# Power.net
KiCad netlist of a schematic drawn in Altium Designer
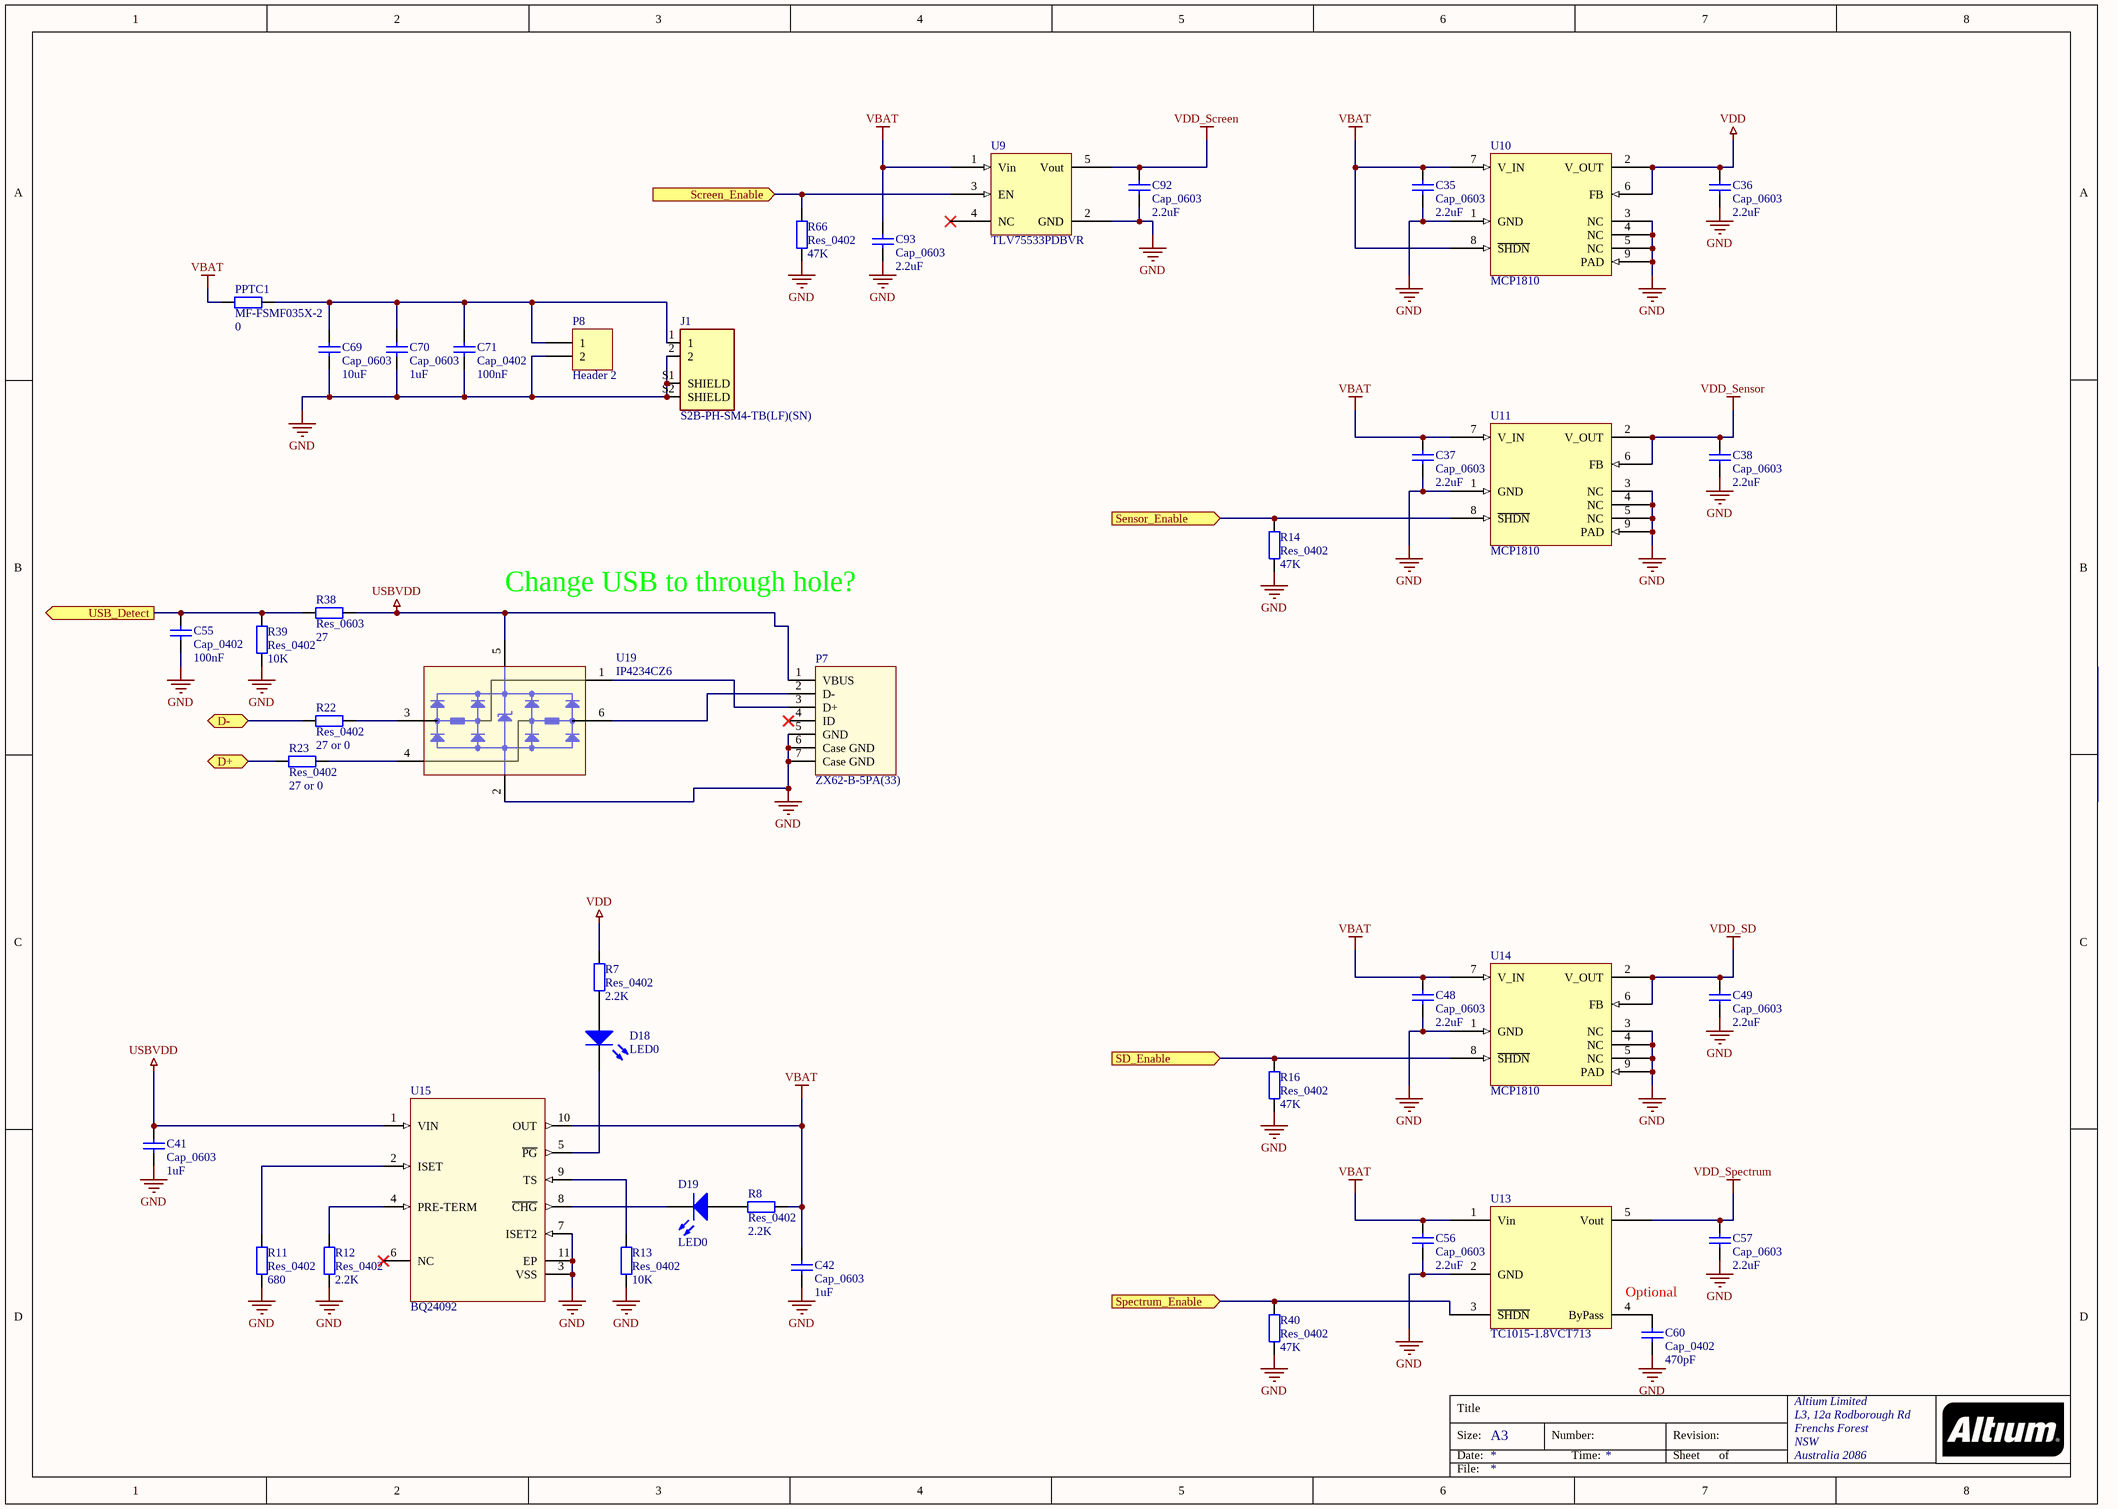
[diagram p0: Power.SchDoc]

(export (version "E")
  (design (tool "Eeschema 10.0.6"))
  (components
    (comp (ref "C35")
      (value "Cap_0603")
      (footprint "0603")
      (description "Capacitor")
      (fields (field (name "ALTIUM_VALUE") "2.2uF") (field (name "PUBLISHER") "Altium Limited"))
      (libsource (lib "Schematic_Components") (part "Cap_0603"))
    )
    (comp (ref "C36")
      (value "Cap_0603")
      (footprint "0603")
      (description "Capacitor")
      (fields (field (name "ALTIUM_VALUE") "2.2uF") (field (name "PUBLISHER") "Altium Limited"))
      (libsource (lib "Schematic_Components") (part "Cap_0603"))
    )
    (comp (ref "C37")
      (value "Cap_0603")
      (footprint "0603")
      (description "Capacitor")
      (fields (field (name "ALTIUM_VALUE") "2.2uF") (field (name "PUBLISHER") "Altium Limited"))
      (libsource (lib "Schematic_Components") (part "Cap_0603"))
    )
    (comp (ref "C38")
      (value "Cap_0603")
      (footprint "0603")
      (description "Capacitor")
      (fields (field (name "ALTIUM_VALUE") "2.2uF") (field (name "PUBLISHER") "Altium Limited"))
      (libsource (lib "Schematic_Components") (part "Cap_0603"))
    )
    (comp (ref "C41")
      (value "Cap_0603")
      (footprint "0603")
      (description "Capacitor")
      (fields (field (name "ALTIUM_VALUE") "1uF") (field (name "PUBLISHER") "Altium Limited"))
      (libsource (lib "Schematic_Components") (part "Cap_0603"))
    )
    (comp (ref "C42")
      (value "Cap_0603")
      (footprint "0603")
      (description "Capacitor")
      (fields (field (name "ALTIUM_VALUE") "1uF") (field (name "PUBLISHER") "Altium Limited"))
      (libsource (lib "Schematic_Components") (part "Cap_0603"))
    )
    (comp (ref "C48")
      (value "Cap_0603")
      (footprint "0603")
      (description "Capacitor")
      (fields (field (name "ALTIUM_VALUE") "2.2uF") (field (name "PUBLISHER") "Altium Limited"))
      (libsource (lib "Schematic_Components") (part "Cap_0603"))
    )
    (comp (ref "C49")
      (value "Cap_0603")
      (footprint "0603")
      (description "Capacitor")
      (fields (field (name "ALTIUM_VALUE") "2.2uF") (field (name "PUBLISHER") "Altium Limited"))
      (libsource (lib "Schematic_Components") (part "Cap_0603"))
    )
    (comp (ref "C55")
      (value "Cap_0402")
      (footprint "0402")
      (description "Capacitor")
      (fields (field (name "ALTIUM_VALUE") "100nF") (field (name "PUBLISHER") "Altium Limited"))
      (libsource (lib "Schematic_Components") (part "Cap_0402"))
    )
    (comp (ref "C56")
      (value "Cap_0603")
      (footprint "0603")
      (description "Capacitor")
      (fields (field (name "ALTIUM_VALUE") "2.2uF") (field (name "PUBLISHER") "Altium Limited"))
      (libsource (lib "Schematic_Components") (part "Cap_0603"))
    )
    (comp (ref "C57")
      (value "Cap_0603")
      (footprint "0603")
      (description "Capacitor")
      (fields (field (name "ALTIUM_VALUE") "2.2uF") (field (name "PUBLISHER") "Altium Limited"))
      (libsource (lib "Schematic_Components") (part "Cap_0603"))
    )
    (comp (ref "C60")
      (value "Cap_0402")
      (footprint "0402")
      (description "Capacitor")
      (fields (field (name "ALTIUM_VALUE") "470pF") (field (name "PUBLISHER") "Altium Limited"))
      (libsource (lib "Schematic_Components") (part "Cap_0402"))
    )
    (comp (ref "C69")
      (value "Cap_0603")
      (footprint "0603")
      (description "Capacitor")
      (fields (field (name "ALTIUM_VALUE") "10uF") (field (name "PUBLISHER") "Altium Limited"))
      (libsource (lib "Schematic_Components") (part "Cap_0603"))
    )
    (comp (ref "C70")
      (value "Cap_0603")
      (footprint "0603")
      (description "Capacitor")
      (fields (field (name "ALTIUM_VALUE") "1uF") (field (name "PUBLISHER") "Altium Limited"))
      (libsource (lib "Schematic_Components") (part "Cap_0603"))
    )
    (comp (ref "C71")
      (value "Cap_0402")
      (footprint "0402")
      (description "Capacitor")
      (fields (field (name "ALTIUM_VALUE") "100nF") (field (name "PUBLISHER") "Altium Limited"))
      (libsource (lib "Schematic_Components") (part "Cap_0402"))
    )
    (comp (ref "C92")
      (value "Cap_0603")
      (footprint "0603")
      (description "Capacitor")
      (fields (field (name "ALTIUM_VALUE") "2.2uF") (field (name "PUBLISHER") "Altium Limited"))
      (libsource (lib "Schematic_Components") (part "Cap_0603"))
    )
    (comp (ref "C93")
      (value "Cap_0603")
      (footprint "0603")
      (description "Capacitor")
      (fields (field (name "ALTIUM_VALUE") "2.2uF") (field (name "PUBLISHER") "Altium Limited"))
      (libsource (lib "Schematic_Components") (part "Cap_0603"))
    )
    (comp (ref "D18")
      (value "LED0")
      (footprint "0603")
      (description "Typical INFRARED GaAs LED")
      (fields (field (name "PUBLISHER") "Altium Limited"))
      (libsource (lib "Schematic_Components") (part "LED0"))
    )
    (comp (ref "D19")
      (value "LED0")
      (footprint "0603")
      (description "Typical INFRARED GaAs LED")
      (fields (field (name "PUBLISHER") "Altium Limited"))
      (libsource (lib "Schematic_Components") (part "LED0"))
    )
    (comp (ref "J1")
      (value "S2B-PH-SM4-TB(LF)(SN)")
      (footprint "JST_S2B-PH-SM4-TB(LF)(SN)")
      (description "PH Series 2 Position 2 mm Pitch Surface Mount Side Entry Shrouded Header")
      (fields (field (name "MF") "{'manufacturer': u'JST Sales'}"))
      (libsource (lib "Schematic_Components") (part "S2B-PH-SM4-TB(LF)(SN)"))
    )
    (comp (ref "P7")
      (value "ZX62-B-5PA(33)")
      (footprint "ZX62-B-5PA(33)")
      (description "USB Connector")
      (libsource (lib "Exeger_schematic_library") (part "ZX62-B-5PA(33)"))
    )
    (comp (ref "P8")
      (value "Header 2")
      (footprint "HDR1X2")
      (description "Header, 2-Pin")
      (fields (field (name "PUBLISHER") "Altium Limited"))
      (libsource (lib "Miscellaneous Connectors") (part "Header 2"))
    )
    (comp (ref "PPTC1")
      (value "MF-FSMF035X-2")
      (footprint "0603")
      (description "PPTC_0603")
      (fields (field (name "ALTIUM_VALUE") "0") (field (name "PUBLISHER") "Altium Limited"))
      (libsource (lib "Schematic_Components") (part "MF-FSMF035X-2"))
    )
    (comp (ref "R7")
      (value "Res_0402")
      (footprint "0402")
      (description "Resistor")
      (fields (field (name "ALTIUM_VALUE") "2.2K") (field (name "PUBLISHER") "Altium Limited"))
      (libsource (lib "") (part "Res_0402_1"))
    )
    (comp (ref "R8")
      (value "Res_0402")
      (footprint "0402")
      (description "Resistor")
      (fields (field (name "ALTIUM_VALUE") "2.2K") (field (name "PUBLISHER") "Altium Limited"))
      (libsource (lib "Schematic_Components") (part "Res_0402"))
    )
    (comp (ref "R11")
      (value "Res_0402")
      (footprint "0402")
      (description "Resistor")
      (fields (field (name "ALTIUM_VALUE") "680") (field (name "PUBLISHER") "Altium Limited"))
      (libsource (lib "") (part "Res_0402_1"))
    )
    (comp (ref "R12")
      (value "Res_0402")
      (footprint "0402")
      (description "Resistor")
      (fields (field (name "ALTIUM_VALUE") "2.2K") (field (name "PUBLISHER") "Altium Limited"))
      (libsource (lib "") (part "Res_0402_1"))
    )
    (comp (ref "R13")
      (value "Res_0402")
      (footprint "0402")
      (description "Resistor")
      (fields (field (name "ALTIUM_VALUE") "10K") (field (name "PUBLISHER") "Altium Limited"))
      (libsource (lib "") (part "Res_0402_1"))
    )
    (comp (ref "R14")
      (value "Res_0402")
      (footprint "0402")
      (description "Resistor")
      (fields (field (name "ALTIUM_VALUE") "47K") (field (name "PUBLISHER") "Altium Limited"))
      (libsource (lib "") (part "Res_0402_3"))
    )
    (comp (ref "R16")
      (value "Res_0402")
      (footprint "0402")
      (description "Resistor")
      (fields (field (name "ALTIUM_VALUE") "47K") (field (name "PUBLISHER") "Altium Limited"))
      (libsource (lib "") (part "Res_0402_1"))
    )
    (comp (ref "R22")
      (value "Res_0402")
      (footprint "0402")
      (description "Resistor")
      (fields (field (name "ALTIUM_VALUE") "27 or 0") (field (name "PUBLISHER") "Altium Limited"))
      (libsource (lib "") (part "Res_0402_2"))
    )
    (comp (ref "R23")
      (value "Res_0402")
      (footprint "0402")
      (description "Resistor")
      (fields (field (name "ALTIUM_VALUE") "27 or 0") (field (name "PUBLISHER") "Altium Limited"))
      (libsource (lib "") (part "Res_0402_2"))
    )
    (comp (ref "R38")
      (value "Res_0603")
      (footprint "0603")
      (description "Resistor")
      (fields (field (name "ALTIUM_VALUE") "27") (field (name "PUBLISHER") "Altium Limited"))
      (libsource (lib "Schematic_Components") (part "Res_0603"))
    )
    (comp (ref "R39")
      (value "Res_0402")
      (footprint "0402")
      (description "Resistor")
      (fields (field (name "ALTIUM_VALUE") "10K") (field (name "PUBLISHER") "Altium Limited"))
      (libsource (lib "") (part "Res_0402_1"))
    )
    (comp (ref "R40")
      (value "Res_0402")
      (footprint "0402")
      (description "Resistor")
      (fields (field (name "ALTIUM_VALUE") "47K") (field (name "PUBLISHER") "Altium Limited"))
      (libsource (lib "") (part "Res_0402_3"))
    )
    (comp (ref "R66")
      (value "Res_0402")
      (footprint "0402")
      (description "Resistor")
      (fields (field (name "ALTIUM_VALUE") "47K") (field (name "PUBLISHER") "Altium Limited"))
      (libsource (lib "") (part "Res_0402_3"))
    )
    (comp (ref "U9")
      (value "TLV75533PDBVR")
      (footprint "SOT-23 (5)")
      (description "3.3V regulator")
      (libsource (lib "Schematic_Components") (part "TLV75533PDBVR"))
    )
    (comp (ref "U10")
      (value "MCP1810")
      (footprint "VDFN8")
      (description "3V Regulator, 150 mA")
      (libsource (lib "Schematic_Components") (part "MCP1810"))
    )
    (comp (ref "U11")
      (value "MCP1810")
      (footprint "VDFN8")
      (description "3V Regulator, 150 mA")
      (libsource (lib "Schematic_Components") (part "MCP1810"))
    )
    (comp (ref "U13")
      (value "TC1015-1.8VCT713")
      (footprint "SOT-23 (5)")
      (description "1.8V Regulator")
      (libsource (lib "Schematic_Components") (part "TC1015-1.8VCT713"))
    )
    (comp (ref "U14")
      (value "MCP1810")
      (footprint "VDFN8")
      (description "3V Regulator, 150 mA")
      (libsource (lib "Schematic_Components") (part "MCP1810"))
    )
    (comp (ref "U15")
      (value "BQ24092")
      (footprint "HVSSOP-10")
      (description "Battery Charger")
      (libsource (lib "Schematic_Components") (part "BQ24092"))
    )
    (comp (ref "U19")
      (value "IP4234CZ6")
      (footprint "TSOP95P280X110_HS-7N")
      (description "USB Line Protection")
      (libsource (lib "Exeger_schematic_library") (part "IP4234CZ6"))
    )
  )
  (nets
    (net (code "1") (name "/D+") (class "Default")
      (node (ref "R23") (pin "1") (pinfunction "1_1") (pintype "passive"))
    )
    (net (code "2") (name "/D-") (class "Default")
      (node (ref "R22") (pin "1") (pinfunction "1_1") (pintype "passive"))
    )
    (net (code "3") (name "/SD_Enable") (class "Default")
      (node (ref "R16") (pin "2") (pinfunction "2_2") (pintype "passive"))
      (node (ref "U14") (pin "8") (pinfunction "~{SHDN}_8") (pintype "input"))
    )
    (net (code "4") (name "/Screen_Enable") (class "Default")
      (node (ref "R66") (pin "1") (pinfunction "1_1") (pintype "passive"))
      (node (ref "U9") (pin "3") (pinfunction "EN_3") (pintype "input"))
    )
    (net (code "5") (name "/Sensor_Enable") (class "Default")
      (node (ref "R14") (pin "1") (pinfunction "1_1") (pintype "passive"))
      (node (ref "U11") (pin "8") (pinfunction "~{SHDN}_8") (pintype "input"))
    )
    (net (code "6") (name "/Spectrum_Enable") (class "Default")
      (node (ref "R40") (pin "1") (pinfunction "1_1") (pintype "passive"))
      (node (ref "U13") (pin "3") (pinfunction "~{SHDN}_3") (pintype "passive"))
    )
    (net (code "7") (name "/USB_Detect") (class "Default")
      (node (ref "C55") (pin "2") (pinfunction "2_2") (pintype "passive"))
      (node (ref "R38") (pin "1") (pinfunction "1_1") (pintype "passive"))
      (node (ref "R39") (pin "2") (pinfunction "2_2") (pintype "passive"))
    )
    (net (code "8") (name "GND") (class "Default")
      (node (ref "C35") (pin "1") (pinfunction "1_1") (pintype "passive"))
      (node (ref "C36") (pin "1") (pinfunction "1_1") (pintype "passive"))
      (node (ref "C37") (pin "1") (pinfunction "1_1") (pintype "passive"))
      (node (ref "C38") (pin "1") (pinfunction "1_1") (pintype "passive"))
      (node (ref "C41") (pin "1") (pinfunction "1_1") (pintype "passive"))
      (node (ref "C42") (pin "1") (pinfunction "1_1") (pintype "passive"))
      (node (ref "C48") (pin "1") (pinfunction "1_1") (pintype "passive"))
      (node (ref "C49") (pin "1") (pinfunction "1_1") (pintype "passive"))
      (node (ref "C55") (pin "1") (pinfunction "1_1") (pintype "passive"))
      (node (ref "C56") (pin "1") (pinfunction "1_1") (pintype "passive"))
      (node (ref "C57") (pin "1") (pinfunction "1_1") (pintype "passive"))
      (node (ref "C60") (pin "1") (pinfunction "1_1") (pintype "passive"))
      (node (ref "C69") (pin "1") (pinfunction "1_1") (pintype "passive"))
      (node (ref "C70") (pin "1") (pinfunction "1_1") (pintype "passive"))
      (node (ref "C71") (pin "1") (pinfunction "1_1") (pintype "passive"))
      (node (ref "C92") (pin "1") (pinfunction "1_1") (pintype "passive"))
      (node (ref "C93") (pin "1") (pinfunction "1_1") (pintype "passive"))
      (node (ref "J1") (pin "2") (pinfunction "2_2") (pintype "passive"))
      (node (ref "J1") (pin "S1") (pinfunction "SHIELD_S1") (pintype "passive"))
      (node (ref "J1") (pin "S2") (pinfunction "SHIELD_S2") (pintype "passive"))
      (node (ref "P7") (pin "5") (pinfunction "GND_5") (pintype "power_in"))
      (node (ref "P7") (pin "6") (pinfunction "Case_GND_6") (pintype "power_in"))
      (node (ref "P7") (pin "7") (pinfunction "Case_GND_7") (pintype "passive"))
      (node (ref "P8") (pin "2") (pinfunction "2_2") (pintype "passive"))
      (node (ref "R11") (pin "1") (pinfunction "1_1") (pintype "passive"))
      (node (ref "R12") (pin "1") (pinfunction "1_1") (pintype "passive"))
      (node (ref "R13") (pin "1") (pinfunction "1_1") (pintype "passive"))
      (node (ref "R14") (pin "2") (pinfunction "2_2") (pintype "passive"))
      (node (ref "R16") (pin "1") (pinfunction "1_1") (pintype "passive"))
      (node (ref "R39") (pin "1") (pinfunction "1_1") (pintype "passive"))
      (node (ref "R40") (pin "2") (pinfunction "2_2") (pintype "passive"))
      (node (ref "R66") (pin "2") (pinfunction "2_2") (pintype "passive"))
      (node (ref "U10") (pin "1") (pinfunction "GND_1") (pintype "input"))
      (node (ref "U10") (pin "3") (pinfunction "NC_3") (pintype "passive"))
      (node (ref "U10") (pin "4") (pinfunction "NC_4") (pintype "passive"))
      (node (ref "U10") (pin "5") (pinfunction "NC_5") (pintype "passive"))
      (node (ref "U10") (pin "9") (pinfunction "PAD_9") (pintype "input"))
      (node (ref "U11") (pin "1") (pinfunction "GND_1") (pintype "input"))
      (node (ref "U11") (pin "3") (pinfunction "NC_3") (pintype "passive"))
      (node (ref "U11") (pin "4") (pinfunction "NC_4") (pintype "passive"))
      (node (ref "U11") (pin "5") (pinfunction "NC_5") (pintype "passive"))
      (node (ref "U11") (pin "9") (pinfunction "PAD_9") (pintype "input"))
      (node (ref "U13") (pin "2") (pinfunction "GND_2") (pintype "passive"))
      (node (ref "U14") (pin "1") (pinfunction "GND_1") (pintype "input"))
      (node (ref "U14") (pin "3") (pinfunction "NC_3") (pintype "passive"))
      (node (ref "U14") (pin "4") (pinfunction "NC_4") (pintype "passive"))
      (node (ref "U14") (pin "5") (pinfunction "NC_5") (pintype "passive"))
      (node (ref "U14") (pin "9") (pinfunction "PAD_9") (pintype "input"))
      (node (ref "U15") (pin "11") (pinfunction "EP_11") (pintype "power_in"))
      (node (ref "U15") (pin "3") (pinfunction "VSS_3") (pintype "power_in"))
      (node (ref "U15") (pin "7") (pinfunction "ISET2_7") (pintype "input"))
      (node (ref "U19") (pin "2") (pinfunction "GND_2") (pintype "power_in"))
      (node (ref "U9") (pin "2") (pinfunction "GND_2") (pintype "passive"))
    )
    (net (code "9") (name "Net-(C69-Pad2)") (class "Default")
      (node (ref "C69") (pin "2") (pinfunction "2_2") (pintype "passive"))
      (node (ref "C70") (pin "2") (pinfunction "2_2") (pintype "passive"))
      (node (ref "C71") (pin "2") (pinfunction "2_2") (pintype "passive"))
      (node (ref "J1") (pin "1") (pinfunction "1_1") (pintype "passive"))
      (node (ref "P8") (pin "1") (pinfunction "1_1") (pintype "passive"))
      (node (ref "PPTC1") (pin "2") (pinfunction "2_2") (pintype "passive"))
    )
    (net (code "10") (name "Net-(D18-A)") (class "Default")
      (node (ref "D18") (pin "2") (pinfunction "A_2") (pintype "passive"))
      (node (ref "R7") (pin "1") (pinfunction "1_1") (pintype "passive"))
    )
    (net (code "11") (name "Net-(D18-K)") (class "Default")
      (node (ref "D18") (pin "1") (pinfunction "K_1") (pintype "passive"))
      (node (ref "U15") (pin "5") (pinfunction "~{PG}_5") (pintype "output"))
    )
    (net (code "12") (name "Net-(D19-A)") (class "Default")
      (node (ref "D19") (pin "2") (pinfunction "A_2") (pintype "passive"))
      (node (ref "R8") (pin "2") (pinfunction "2_2") (pintype "passive"))
    )
    (net (code "13") (name "Net-(D19-K)") (class "Default")
      (node (ref "D19") (pin "1") (pinfunction "K_1") (pintype "passive"))
      (node (ref "U15") (pin "8") (pinfunction "~{CHG}_8") (pintype "output"))
    )
    (net (code "14") (name "Net-(P7-D+)") (class "Default")
      (node (ref "P7") (pin "3") (pinfunction "D+_3") (pintype "passive"))
      (node (ref "U19") (pin "1") (pinfunction "CH1_A_1") (pintype "passive"))
    )
    (net (code "15") (name "Net-(P7-D-)") (class "Default")
      (node (ref "P7") (pin "2") (pinfunction "D-_2") (pintype "passive"))
      (node (ref "U19") (pin "6") (pinfunction "CH2_B_6") (pintype "passive"))
    )
    (net (code "16") (name "Net-(U13-ByPass)") (class "Default")
      (node (ref "C60") (pin "2") (pinfunction "2_2") (pintype "passive"))
      (node (ref "U13") (pin "4") (pinfunction "ByPass_4") (pintype "passive"))
    )
    (net (code "17") (name "Net-(U15-ISET)") (class "Default")
      (node (ref "R11") (pin "2") (pinfunction "2_2") (pintype "passive"))
      (node (ref "U15") (pin "2") (pinfunction "ISET_2") (pintype "input"))
    )
    (net (code "18") (name "Net-(U15-PRE-TERM)") (class "Default")
      (node (ref "R12") (pin "2") (pinfunction "2_2") (pintype "passive"))
      (node (ref "U15") (pin "4") (pinfunction "PRE-TERM_4") (pintype "input"))
    )
    (net (code "19") (name "Net-(U15-TS)") (class "Default")
      (node (ref "R13") (pin "2") (pinfunction "2_2") (pintype "passive"))
      (node (ref "U15") (pin "9") (pinfunction "TS_9") (pintype "input"))
    )
    (net (code "20") (name "Net-(U19-CH1_B)") (class "Default")
      (node (ref "R22") (pin "2") (pinfunction "2_2") (pintype "passive"))
      (node (ref "U19") (pin "3") (pinfunction "CH1_B_3") (pintype "passive"))
    )
    (net (code "21") (name "Net-(U19-CH2_A)") (class "Default")
      (node (ref "R23") (pin "2") (pinfunction "2_2") (pintype "passive"))
      (node (ref "U19") (pin "4") (pinfunction "CH2_A_4") (pintype "passive"))
    )
    (net (code "22") (name "USBVDD") (class "Default")
      (node (ref "C41") (pin "2") (pinfunction "2_2") (pintype "passive"))
      (node (ref "P7") (pin "1") (pinfunction "VBUS_1") (pintype "power_in"))
      (node (ref "R38") (pin "2") (pinfunction "2_2") (pintype "passive"))
      (node (ref "U15") (pin "1") (pinfunction "VIN_1") (pintype "input"))
      (node (ref "U19") (pin "5") (pinfunction "VCC_5") (pintype "power_in"))
    )
    (net (code "23") (name "VBAT") (class "Default")
      (node (ref "C35") (pin "2") (pinfunction "2_2") (pintype "passive"))
      (node (ref "C37") (pin "2") (pinfunction "2_2") (pintype "passive"))
      (node (ref "C42") (pin "2") (pinfunction "2_2") (pintype "passive"))
      (node (ref "C48") (pin "2") (pinfunction "2_2") (pintype "passive"))
      (node (ref "C56") (pin "2") (pinfunction "2_2") (pintype "passive"))
      (node (ref "C93") (pin "2") (pinfunction "2_2") (pintype "passive"))
      (node (ref "PPTC1") (pin "1") (pinfunction "1_1") (pintype "passive"))
      (node (ref "R8") (pin "1") (pinfunction "1_1") (pintype "passive"))
      (node (ref "U10") (pin "7") (pinfunction "V_IN_7") (pintype "input"))
      (node (ref "U10") (pin "8") (pinfunction "~{SHDN}_8") (pintype "input"))
      (node (ref "U11") (pin "7") (pinfunction "V_IN_7") (pintype "input"))
      (node (ref "U13") (pin "1") (pinfunction "Vin_1") (pintype "passive"))
      (node (ref "U14") (pin "7") (pinfunction "V_IN_7") (pintype "input"))
      (node (ref "U15") (pin "10") (pinfunction "OUT_10") (pintype "output"))
      (node (ref "U9") (pin "1") (pinfunction "Vin_1") (pintype "input"))
    )
    (net (code "24") (name "VDD") (class "Default")
      (node (ref "C36") (pin "2") (pinfunction "2_2") (pintype "passive"))
      (node (ref "R7") (pin "2") (pinfunction "2_2") (pintype "passive"))
      (node (ref "U10") (pin "2") (pinfunction "V_OUT_2") (pintype "passive"))
      (node (ref "U10") (pin "6") (pinfunction "FB_6") (pintype "input"))
    )
    (net (code "25") (name "VDD_SD") (class "Default")
      (node (ref "C49") (pin "2") (pinfunction "2_2") (pintype "passive"))
      (node (ref "U14") (pin "2") (pinfunction "V_OUT_2") (pintype "passive"))
      (node (ref "U14") (pin "6") (pinfunction "FB_6") (pintype "input"))
    )
    (net (code "26") (name "VDD_Screen") (class "Default")
      (node (ref "C92") (pin "2") (pinfunction "2_2") (pintype "passive"))
      (node (ref "U9") (pin "5") (pinfunction "Vout_5") (pintype "passive"))
    )
    (net (code "27") (name "VDD_Sensor") (class "Default")
      (node (ref "C38") (pin "2") (pinfunction "2_2") (pintype "passive"))
      (node (ref "U11") (pin "2") (pinfunction "V_OUT_2") (pintype "passive"))
      (node (ref "U11") (pin "6") (pinfunction "FB_6") (pintype "input"))
    )
    (net (code "28") (name "VDD_Spectrum") (class "Default")
      (node (ref "C57") (pin "2") (pinfunction "2_2") (pintype "passive"))
      (node (ref "U13") (pin "5") (pinfunction "Vout_5") (pintype "passive"))
    )
    (net (code "29") (name "unconnected-(P7-ID-Pad4)") (class "Default")
      (node (ref "P7") (pin "4") (pinfunction "ID_4") (pintype "passive+no_connect"))
    )
    (net (code "30") (name "unconnected-(U9-NC-Pad4)") (class "Default")
      (node (ref "U9") (pin "4") (pinfunction "NC_4") (pintype "passive+no_connect"))
    )
    (net (code "31") (name "unconnected-(U15-NC-Pad6)") (class "Default")
      (node (ref "U15") (pin "6") (pinfunction "NC_6") (pintype "passive+no_connect"))
    )
  )
)
